# IN-12B_breakout.net
KiCad netlist of a schematic drawn in EAGLE
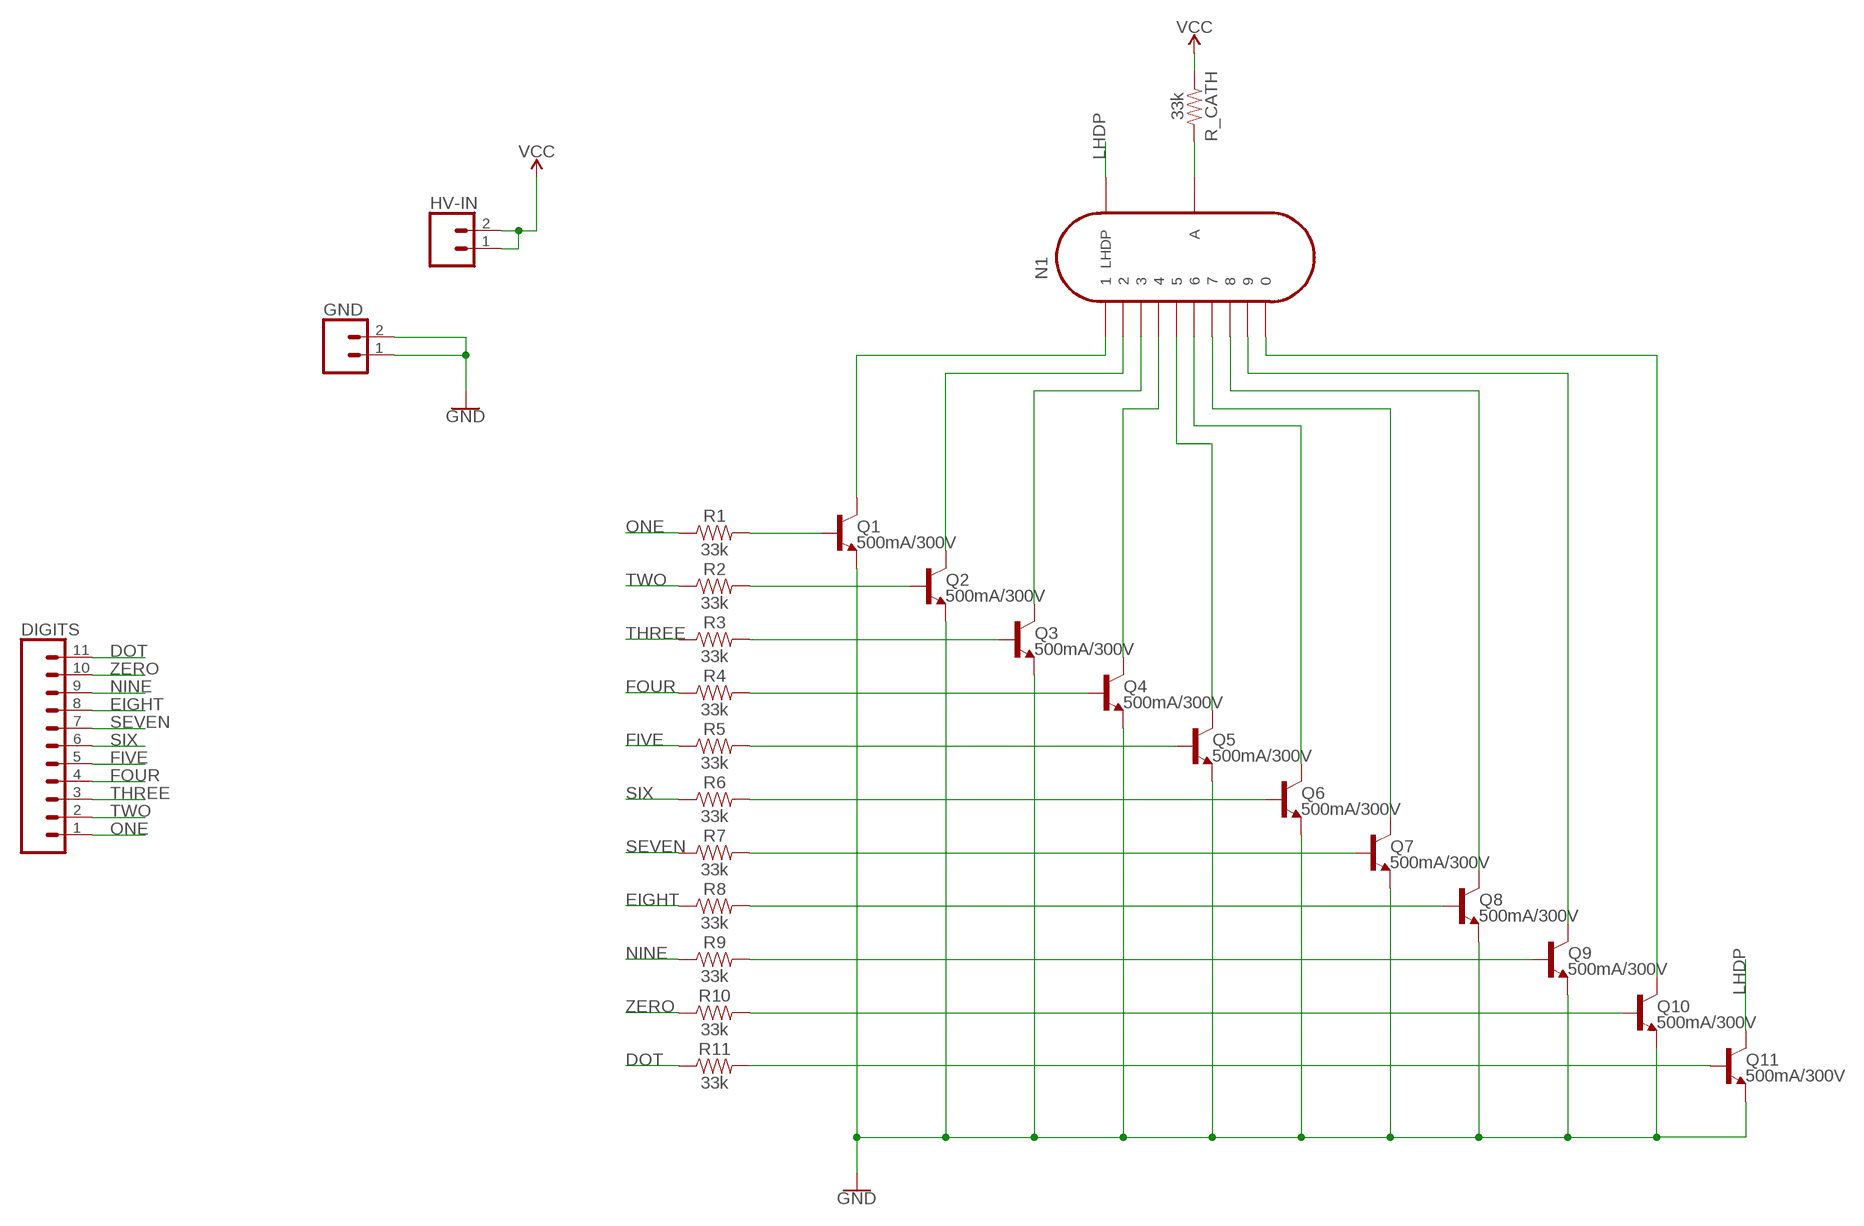
[diagram p0: schematic, sheet 1]

(export (version "E")
  (design (tool "Eeschema 10.0.6"))
  (components
    (comp (ref "DIGITS")
      (value "CONN_11")
      (footprint "eagle-import:1X11")
      (libsource (lib "eagle-import") (part "CONN_11"))
    )
    (comp (ref "GND")
      (value "CONN_02")
      (footprint "eagle-import:1X02")
      (libsource (lib "eagle-import") (part "CONN_02"))
    )
    (comp (ref "HV-IN")
      (value "CONN_02")
      (footprint "eagle-import:1X02")
      (libsource (lib "eagle-import") (part "CONN_02"))
    )
    (comp (ref "N1")
      (value "IN-12B")
      (footprint "eagle-import:IN-12")
      (libsource (lib "eagle-import") (part "IN-12B"))
    )
    (comp (ref "Q1")
      (value "500mA/300V")
      (footprint "eagle-import:SOT23-3")
      (libsource (lib "eagle-import") (part "TRANS_NPN-MMBTA42"))
    )
    (comp (ref "Q2")
      (value "500mA/300V")
      (footprint "eagle-import:SOT23-3")
      (libsource (lib "eagle-import") (part "TRANS_NPN-MMBTA42"))
    )
    (comp (ref "Q3")
      (value "500mA/300V")
      (footprint "eagle-import:SOT23-3")
      (libsource (lib "eagle-import") (part "TRANS_NPN-MMBTA42"))
    )
    (comp (ref "Q4")
      (value "500mA/300V")
      (footprint "eagle-import:SOT23-3")
      (libsource (lib "eagle-import") (part "TRANS_NPN-MMBTA42"))
    )
    (comp (ref "Q5")
      (value "500mA/300V")
      (footprint "eagle-import:SOT23-3")
      (libsource (lib "eagle-import") (part "TRANS_NPN-MMBTA42"))
    )
    (comp (ref "Q6")
      (value "500mA/300V")
      (footprint "eagle-import:SOT23-3")
      (libsource (lib "eagle-import") (part "TRANS_NPN-MMBTA42"))
    )
    (comp (ref "Q7")
      (value "500mA/300V")
      (footprint "eagle-import:SOT23-3")
      (libsource (lib "eagle-import") (part "TRANS_NPN-MMBTA42"))
    )
    (comp (ref "Q8")
      (value "500mA/300V")
      (footprint "eagle-import:SOT23-3")
      (libsource (lib "eagle-import") (part "TRANS_NPN-MMBTA42"))
    )
    (comp (ref "Q9")
      (value "500mA/300V")
      (footprint "eagle-import:SOT23-3")
      (libsource (lib "eagle-import") (part "TRANS_NPN-MMBTA42"))
    )
    (comp (ref "Q10")
      (value "500mA/300V")
      (footprint "eagle-import:SOT23-3")
      (libsource (lib "eagle-import") (part "TRANS_NPN-MMBTA42"))
    )
    (comp (ref "Q11")
      (value "500mA/300V")
      (footprint "eagle-import:SOT23-3")
      (libsource (lib "eagle-import") (part "TRANS_NPN-MMBTA42"))
    )
    (comp (ref "R1")
      (value "33k")
      (footprint "eagle-import:0603")
      (libsource (lib "eagle-import") (part "33KOHM-0603-1/10W-1%"))
    )
    (comp (ref "R2")
      (value "33k")
      (footprint "eagle-import:0603")
      (libsource (lib "eagle-import") (part "33KOHM-0603-1/10W-1%"))
    )
    (comp (ref "R3")
      (value "33k")
      (footprint "eagle-import:0603")
      (libsource (lib "eagle-import") (part "33KOHM-0603-1/10W-1%"))
    )
    (comp (ref "R4")
      (value "33k")
      (footprint "eagle-import:0603")
      (libsource (lib "eagle-import") (part "33KOHM-0603-1/10W-1%"))
    )
    (comp (ref "R5")
      (value "33k")
      (footprint "eagle-import:0603")
      (libsource (lib "eagle-import") (part "33KOHM-0603-1/10W-1%"))
    )
    (comp (ref "R6")
      (value "33k")
      (footprint "eagle-import:0603")
      (libsource (lib "eagle-import") (part "33KOHM-0603-1/10W-1%"))
    )
    (comp (ref "R7")
      (value "33k")
      (footprint "eagle-import:0603")
      (libsource (lib "eagle-import") (part "33KOHM-0603-1/10W-1%"))
    )
    (comp (ref "R8")
      (value "33k")
      (footprint "eagle-import:0603")
      (libsource (lib "eagle-import") (part "33KOHM-0603-1/10W-1%"))
    )
    (comp (ref "R9")
      (value "33k")
      (footprint "eagle-import:0603")
      (libsource (lib "eagle-import") (part "33KOHM-0603-1/10W-1%"))
    )
    (comp (ref "R10")
      (value "33k")
      (footprint "eagle-import:0603")
      (libsource (lib "eagle-import") (part "33KOHM-0603-1/10W-1%"))
    )
    (comp (ref "R11")
      (value "33k")
      (footprint "eagle-import:0603")
      (libsource (lib "eagle-import") (part "33KOHM-0603-1/10W-1%"))
    )
    (comp (ref "R_CATH")
      (value "33k")
      (footprint "eagle-import:0603")
      (libsource (lib "eagle-import") (part "33KOHM-0603-1/10W-1%"))
    )
  )
  (nets
    (net (code "1") (name "/DOT") (class "Default")
      (node (ref "DIGITS") (pin "11") (pinfunction "11_11") (pintype "passive"))
      (node (ref "R11") (pin "1") (pinfunction "1_1") (pintype "passive"))
    )
    (net (code "2") (name "/EIGHT") (class "Default")
      (node (ref "DIGITS") (pin "8") (pinfunction "8_8") (pintype "passive"))
      (node (ref "R8") (pin "1") (pinfunction "1_1") (pintype "passive"))
    )
    (net (code "3") (name "/FIVE") (class "Default")
      (node (ref "DIGITS") (pin "5") (pinfunction "5_5") (pintype "passive"))
      (node (ref "R5") (pin "1") (pinfunction "1_1") (pintype "passive"))
    )
    (net (code "4") (name "/FOUR") (class "Default")
      (node (ref "DIGITS") (pin "4") (pinfunction "4_4") (pintype "passive"))
      (node (ref "R4") (pin "1") (pinfunction "1_1") (pintype "passive"))
    )
    (net (code "5") (name "/LHDP") (class "Default")
      (node (ref "N1") (pin "LHDP") (pinfunction "LHDP_LHDP") (pintype "bidirectional"))
      (node (ref "Q11") (pin "3") (pinfunction "C_3") (pintype "passive"))
    )
    (net (code "6") (name "/NINE") (class "Default")
      (node (ref "DIGITS") (pin "9") (pinfunction "9_9") (pintype "passive"))
      (node (ref "R9") (pin "1") (pinfunction "1_1") (pintype "passive"))
    )
    (net (code "7") (name "/ONE") (class "Default")
      (node (ref "DIGITS") (pin "1") (pinfunction "1_1") (pintype "passive"))
      (node (ref "R1") (pin "1") (pinfunction "1_1") (pintype "passive"))
    )
    (net (code "8") (name "/SEVEN") (class "Default")
      (node (ref "DIGITS") (pin "7") (pinfunction "7_7") (pintype "passive"))
      (node (ref "R7") (pin "1") (pinfunction "1_1") (pintype "passive"))
    )
    (net (code "9") (name "/SIX") (class "Default")
      (node (ref "DIGITS") (pin "6") (pinfunction "6_6") (pintype "passive"))
      (node (ref "R6") (pin "1") (pinfunction "1_1") (pintype "passive"))
    )
    (net (code "10") (name "/THREE") (class "Default")
      (node (ref "DIGITS") (pin "3") (pinfunction "3_3") (pintype "passive"))
      (node (ref "R3") (pin "1") (pinfunction "1_1") (pintype "passive"))
    )
    (net (code "11") (name "/TWO") (class "Default")
      (node (ref "DIGITS") (pin "2") (pinfunction "2_2") (pintype "passive"))
      (node (ref "R2") (pin "1") (pinfunction "1_1") (pintype "passive"))
    )
    (net (code "12") (name "/ZERO") (class "Default")
      (node (ref "DIGITS") (pin "10") (pinfunction "10_10") (pintype "passive"))
      (node (ref "R10") (pin "1") (pinfunction "1_1") (pintype "passive"))
    )
    (net (code "13") (name "GND") (class "Default")
      (node (ref "GND") (pin "1") (pinfunction "1_1") (pintype "passive"))
      (node (ref "GND") (pin "2") (pinfunction "2_2") (pintype "passive"))
      (node (ref "Q1") (pin "2") (pinfunction "E_2") (pintype "passive"))
      (node (ref "Q10") (pin "2") (pinfunction "E_2") (pintype "passive"))
      (node (ref "Q11") (pin "2") (pinfunction "E_2") (pintype "passive"))
      (node (ref "Q2") (pin "2") (pinfunction "E_2") (pintype "passive"))
      (node (ref "Q3") (pin "2") (pinfunction "E_2") (pintype "passive"))
      (node (ref "Q4") (pin "2") (pinfunction "E_2") (pintype "passive"))
      (node (ref "Q5") (pin "2") (pinfunction "E_2") (pintype "passive"))
      (node (ref "Q6") (pin "2") (pinfunction "E_2") (pintype "passive"))
      (node (ref "Q7") (pin "2") (pinfunction "E_2") (pintype "passive"))
      (node (ref "Q8") (pin "2") (pinfunction "E_2") (pintype "passive"))
      (node (ref "Q9") (pin "2") (pinfunction "E_2") (pintype "passive"))
    )
    (net (code "14") (name "Net-(N1-PadA)") (class "Default")
      (node (ref "N1") (pin "A") (pinfunction "A_A") (pintype "bidirectional"))
      (node (ref "R_CATH") (pin "2") (pinfunction "2_2") (pintype "passive"))
    )
    (net (code "15") (name "Net-(Q1-B)") (class "Default")
      (node (ref "Q1") (pin "1") (pinfunction "B_1") (pintype "passive"))
      (node (ref "R1") (pin "2") (pinfunction "2_2") (pintype "passive"))
    )
    (net (code "16") (name "Net-(Q1-C)") (class "Default")
      (node (ref "N1") (pin "1") (pinfunction "1_1") (pintype "bidirectional"))
      (node (ref "Q1") (pin "3") (pinfunction "C_3") (pintype "passive"))
    )
    (net (code "17") (name "Net-(Q2-B)") (class "Default")
      (node (ref "Q2") (pin "1") (pinfunction "B_1") (pintype "passive"))
      (node (ref "R2") (pin "2") (pinfunction "2_2") (pintype "passive"))
    )
    (net (code "18") (name "Net-(Q2-C)") (class "Default")
      (node (ref "N1") (pin "2") (pinfunction "2_2") (pintype "bidirectional"))
      (node (ref "Q2") (pin "3") (pinfunction "C_3") (pintype "passive"))
    )
    (net (code "19") (name "Net-(Q3-B)") (class "Default")
      (node (ref "Q3") (pin "1") (pinfunction "B_1") (pintype "passive"))
      (node (ref "R3") (pin "2") (pinfunction "2_2") (pintype "passive"))
    )
    (net (code "20") (name "Net-(Q3-C)") (class "Default")
      (node (ref "N1") (pin "3") (pinfunction "3_3") (pintype "bidirectional"))
      (node (ref "Q3") (pin "3") (pinfunction "C_3") (pintype "passive"))
    )
    (net (code "21") (name "Net-(Q4-B)") (class "Default")
      (node (ref "Q4") (pin "1") (pinfunction "B_1") (pintype "passive"))
      (node (ref "R4") (pin "2") (pinfunction "2_2") (pintype "passive"))
    )
    (net (code "22") (name "Net-(Q4-C)") (class "Default")
      (node (ref "N1") (pin "4") (pinfunction "4_4") (pintype "bidirectional"))
      (node (ref "Q4") (pin "3") (pinfunction "C_3") (pintype "passive"))
    )
    (net (code "23") (name "Net-(Q5-B)") (class "Default")
      (node (ref "Q5") (pin "1") (pinfunction "B_1") (pintype "passive"))
      (node (ref "R5") (pin "2") (pinfunction "2_2") (pintype "passive"))
    )
    (net (code "24") (name "Net-(Q5-C)") (class "Default")
      (node (ref "N1") (pin "5") (pinfunction "5_5") (pintype "bidirectional"))
      (node (ref "Q5") (pin "3") (pinfunction "C_3") (pintype "passive"))
    )
    (net (code "25") (name "Net-(Q6-B)") (class "Default")
      (node (ref "Q6") (pin "1") (pinfunction "B_1") (pintype "passive"))
      (node (ref "R6") (pin "2") (pinfunction "2_2") (pintype "passive"))
    )
    (net (code "26") (name "Net-(Q6-C)") (class "Default")
      (node (ref "N1") (pin "6") (pinfunction "6_6") (pintype "bidirectional"))
      (node (ref "Q6") (pin "3") (pinfunction "C_3") (pintype "passive"))
    )
    (net (code "27") (name "Net-(Q7-B)") (class "Default")
      (node (ref "Q7") (pin "1") (pinfunction "B_1") (pintype "passive"))
      (node (ref "R7") (pin "2") (pinfunction "2_2") (pintype "passive"))
    )
    (net (code "28") (name "Net-(Q7-C)") (class "Default")
      (node (ref "N1") (pin "7") (pinfunction "7_7") (pintype "bidirectional"))
      (node (ref "Q7") (pin "3") (pinfunction "C_3") (pintype "passive"))
    )
    (net (code "29") (name "Net-(Q8-B)") (class "Default")
      (node (ref "Q8") (pin "1") (pinfunction "B_1") (pintype "passive"))
      (node (ref "R8") (pin "2") (pinfunction "2_2") (pintype "passive"))
    )
    (net (code "30") (name "Net-(Q8-C)") (class "Default")
      (node (ref "N1") (pin "8") (pinfunction "8_8") (pintype "bidirectional"))
      (node (ref "Q8") (pin "3") (pinfunction "C_3") (pintype "passive"))
    )
    (net (code "31") (name "Net-(Q9-B)") (class "Default")
      (node (ref "Q9") (pin "1") (pinfunction "B_1") (pintype "passive"))
      (node (ref "R9") (pin "2") (pinfunction "2_2") (pintype "passive"))
    )
    (net (code "32") (name "Net-(Q9-C)") (class "Default")
      (node (ref "N1") (pin "9") (pinfunction "9_9") (pintype "bidirectional"))
      (node (ref "Q9") (pin "3") (pinfunction "C_3") (pintype "passive"))
    )
    (net (code "33") (name "Net-(Q10-B)") (class "Default")
      (node (ref "Q10") (pin "1") (pinfunction "B_1") (pintype "passive"))
      (node (ref "R10") (pin "2") (pinfunction "2_2") (pintype "passive"))
    )
    (net (code "34") (name "Net-(Q10-C)") (class "Default")
      (node (ref "N1") (pin "0") (pinfunction "0_0") (pintype "bidirectional"))
      (node (ref "Q10") (pin "3") (pinfunction "C_3") (pintype "passive"))
    )
    (net (code "35") (name "Net-(Q11-B)") (class "Default")
      (node (ref "Q11") (pin "1") (pinfunction "B_1") (pintype "passive"))
      (node (ref "R11") (pin "2") (pinfunction "2_2") (pintype "passive"))
    )
    (net (code "36") (name "VCC") (class "Default")
      (node (ref "HV-IN") (pin "1") (pinfunction "1_1") (pintype "passive"))
      (node (ref "HV-IN") (pin "2") (pinfunction "2_2") (pintype "passive"))
      (node (ref "R_CATH") (pin "1") (pinfunction "1_1") (pintype "passive"))
    )
  )
)
